# uart.net
KiCad netlist of a schematic drawn in Altium Designer
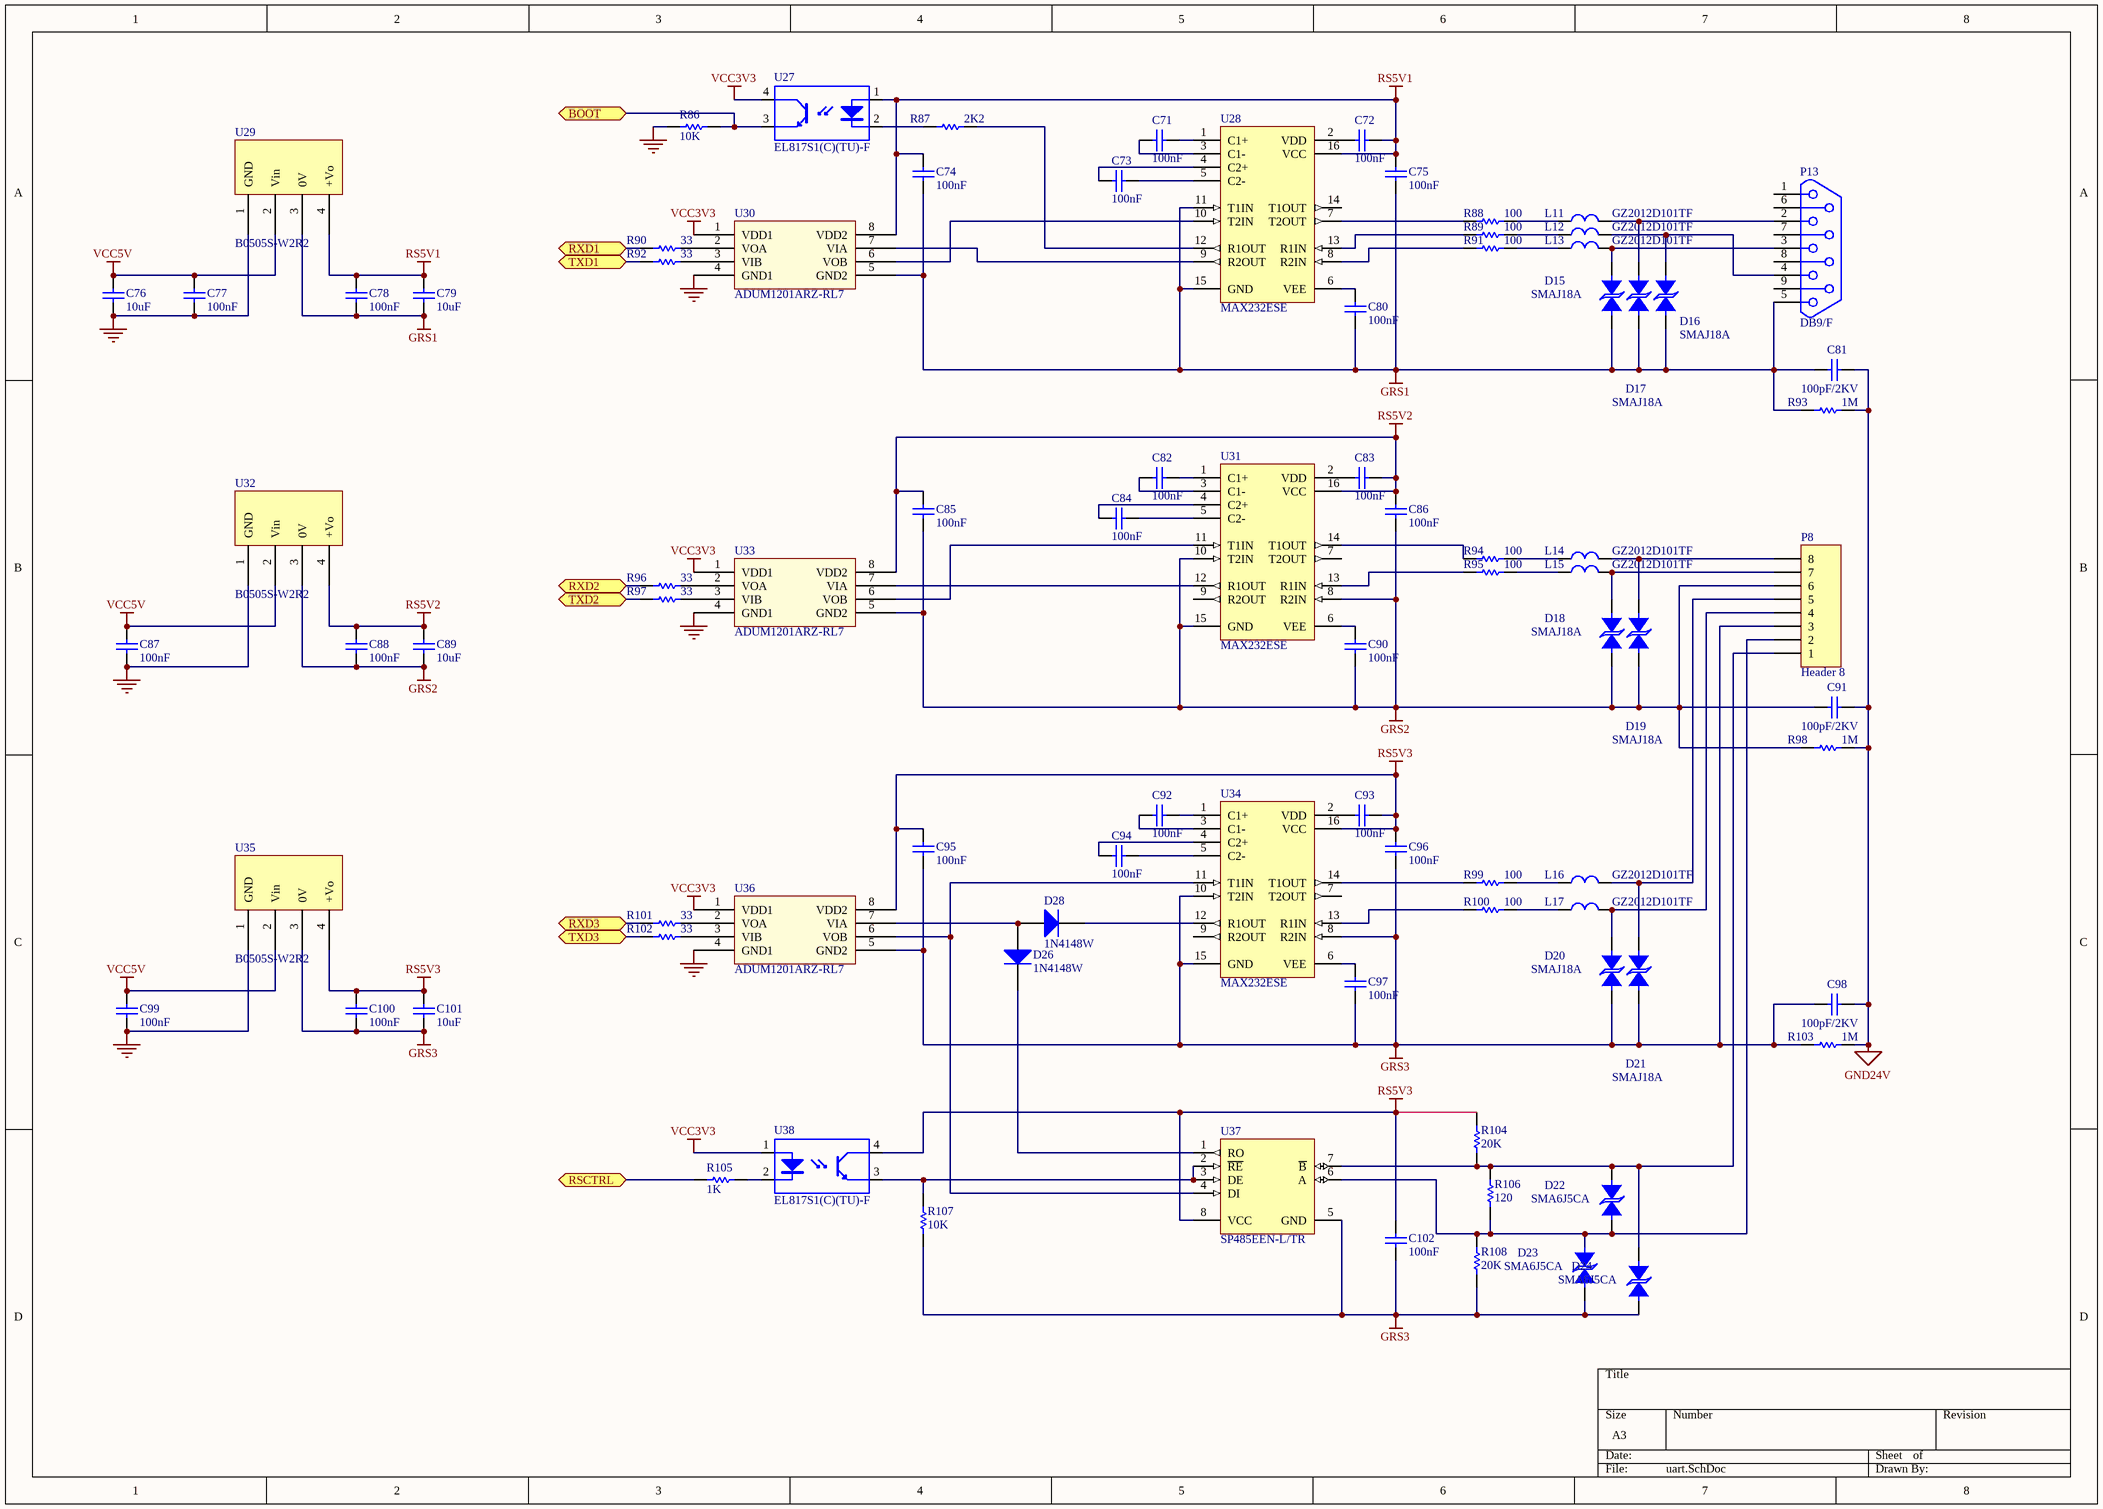
[diagram p0: uart.SchDoc]

(export (version "E")
  (design (tool "Eeschema 10.0.6"))
  (components
    (comp (ref "C71")
      (value "100nF")
      (footprint "0805_C")
      (description "贴片电容")
      (libsource (lib "Miscellaneous Devices LC") (part "0805 100nF(104) 10% 50V"))
    )
    (comp (ref "C72")
      (value "100nF")
      (footprint "0805_C")
      (description "贴片电容")
      (libsource (lib "Miscellaneous Devices LC") (part "0805 100nF(104) 10% 50V"))
    )
    (comp (ref "C73")
      (value "100nF")
      (footprint "0805_C")
      (description "贴片电容")
      (libsource (lib "Miscellaneous Devices LC") (part "0805 100nF(104) 10% 50V"))
    )
    (comp (ref "C74")
      (value "100nF")
      (footprint "0805_C")
      (description "贴片电容")
      (libsource (lib "Miscellaneous Devices LC") (part "0805 100nF(104) 10% 50V"))
    )
    (comp (ref "C75")
      (value "100nF")
      (footprint "0805_C")
      (description "贴片电容")
      (libsource (lib "Miscellaneous Devices LC") (part "0805 100nF(104) 10% 50V"))
    )
    (comp (ref "C76")
      (value "10uF")
      (footprint "0805_C")
      (description "贴片电容")
      (libsource (lib "Miscellaneous Devices LC") (part "0805 10uF (106) 10% 25V"))
    )
    (comp (ref "C77")
      (value "100nF")
      (footprint "0805_C")
      (description "贴片电容")
      (libsource (lib "Miscellaneous Devices LC") (part "0805 100nF(104) 10% 50V"))
    )
    (comp (ref "C78")
      (value "100nF")
      (footprint "0805_C")
      (description "贴片电容")
      (libsource (lib "Miscellaneous Devices LC") (part "0805 100nF(104) 10% 50V"))
    )
    (comp (ref "C79")
      (value "10uF")
      (footprint "0805_C")
      (description "贴片电容")
      (libsource (lib "Miscellaneous Devices LC") (part "0805 10uF (106) 10% 25V"))
    )
    (comp (ref "C80")
      (value "100nF")
      (footprint "0805_C")
      (description "贴片电容")
      (libsource (lib "Miscellaneous Devices LC") (part "0805 100nF(104) 10% 50V"))
    )
    (comp (ref "C81")
      (value "100pF/2KV")
      (footprint "1206_C")
      (description "Capacitor")
      (fields (field (name "PUBLISHER") "Altium Limited"))
      (libsource (lib "Miscellaneous Devices") (part "Cap"))
    )
    (comp (ref "C82")
      (value "100nF")
      (footprint "0805_C")
      (description "贴片电容")
      (libsource (lib "Miscellaneous Devices LC") (part "0805 100nF(104) 10% 50V"))
    )
    (comp (ref "C83")
      (value "100nF")
      (footprint "0805_C")
      (description "贴片电容")
      (libsource (lib "Miscellaneous Devices LC") (part "0805 100nF(104) 10% 50V"))
    )
    (comp (ref "C84")
      (value "100nF")
      (footprint "0805_C")
      (description "贴片电容")
      (libsource (lib "Miscellaneous Devices LC") (part "0805 100nF(104) 10% 50V"))
    )
    (comp (ref "C85")
      (value "100nF")
      (footprint "0805_C")
      (description "贴片电容")
      (libsource (lib "Miscellaneous Devices LC") (part "0805 100nF(104) 10% 50V"))
    )
    (comp (ref "C86")
      (value "100nF")
      (footprint "0805_C")
      (description "贴片电容")
      (libsource (lib "Miscellaneous Devices LC") (part "0805 100nF(104) 10% 50V"))
    )
    (comp (ref "C87")
      (value "100nF")
      (footprint "0805_C")
      (description "贴片电容")
      (libsource (lib "Miscellaneous Devices LC") (part "0805 100nF(104) 10% 50V"))
    )
    (comp (ref "C88")
      (value "100nF")
      (footprint "0805_C")
      (description "贴片电容")
      (libsource (lib "Miscellaneous Devices LC") (part "0805 100nF(104) 10% 50V"))
    )
    (comp (ref "C89")
      (value "10uF")
      (footprint "0805_C")
      (description "贴片电容")
      (libsource (lib "Miscellaneous Devices LC") (part "0805 10uF (106) 10% 25V"))
    )
    (comp (ref "C90")
      (value "100nF")
      (footprint "0805_C")
      (description "贴片电容")
      (libsource (lib "Miscellaneous Devices LC") (part "0805 100nF(104) 10% 50V"))
    )
    (comp (ref "C91")
      (value "100pF/2KV")
      (footprint "1206_C")
      (description "Capacitor")
      (fields (field (name "PUBLISHER") "Altium Limited"))
      (libsource (lib "Miscellaneous Devices") (part "Cap"))
    )
    (comp (ref "C92")
      (value "100nF")
      (footprint "0805_C")
      (description "贴片电容")
      (libsource (lib "Miscellaneous Devices LC") (part "0805 100nF(104) 10% 50V"))
    )
    (comp (ref "C93")
      (value "100nF")
      (footprint "0805_C")
      (description "贴片电容")
      (libsource (lib "Miscellaneous Devices LC") (part "0805 100nF(104) 10% 50V"))
    )
    (comp (ref "C94")
      (value "100nF")
      (footprint "0805_C")
      (description "贴片电容")
      (libsource (lib "Miscellaneous Devices LC") (part "0805 100nF(104) 10% 50V"))
    )
    (comp (ref "C95")
      (value "100nF")
      (footprint "0805_C")
      (description "贴片电容")
      (libsource (lib "Miscellaneous Devices LC") (part "0805 100nF(104) 10% 50V"))
    )
    (comp (ref "C96")
      (value "100nF")
      (footprint "0805_C")
      (description "贴片电容")
      (libsource (lib "Miscellaneous Devices LC") (part "0805 100nF(104) 10% 50V"))
    )
    (comp (ref "C97")
      (value "100nF")
      (footprint "0805_C")
      (description "贴片电容")
      (libsource (lib "Miscellaneous Devices LC") (part "0805 100nF(104) 10% 50V"))
    )
    (comp (ref "C98")
      (value "100pF/2KV")
      (footprint "1206_C")
      (description "Capacitor")
      (fields (field (name "PUBLISHER") "Altium Limited"))
      (libsource (lib "Miscellaneous Devices") (part "Cap"))
    )
    (comp (ref "C99")
      (value "100nF")
      (footprint "0805_C")
      (description "贴片电容")
      (libsource (lib "Miscellaneous Devices LC") (part "0805 100nF(104) 10% 50V"))
    )
    (comp (ref "C100")
      (value "100nF")
      (footprint "0805_C")
      (description "贴片电容")
      (libsource (lib "Miscellaneous Devices LC") (part "0805 100nF(104) 10% 50V"))
    )
    (comp (ref "C101")
      (value "10uF")
      (footprint "0805_C")
      (description "贴片电容")
      (libsource (lib "Miscellaneous Devices LC") (part "0805 10uF (106) 10% 25V"))
    )
    (comp (ref "C102")
      (value "100nF")
      (footprint "0805_C")
      (description "贴片电容")
      (libsource (lib "Miscellaneous Devices LC") (part "0805 100nF(104) 10% 50V"))
    )
    (comp (ref "D15")
      (value "SMAJ18A")
      (footprint "SMA")
      (description "1V5KE6V8CA")
      (libsource (lib "Schlib1") (part "Bidirectional DIODE TVS"))
    )
    (comp (ref "D16")
      (value "SMAJ18A")
      (footprint "SMA")
      (description "1V5KE6V8CA")
      (libsource (lib "Schlib1") (part "Bidirectional DIODE TVS"))
    )
    (comp (ref "D17")
      (value "SMAJ18A")
      (footprint "SMA")
      (description "1V5KE6V8CA")
      (libsource (lib "Schlib1") (part "Bidirectional DIODE TVS"))
    )
    (comp (ref "D18")
      (value "SMAJ18A")
      (footprint "SMA")
      (description "1V5KE6V8CA")
      (libsource (lib "Schlib1") (part "Bidirectional DIODE TVS"))
    )
    (comp (ref "D19")
      (value "SMAJ18A")
      (footprint "SMA")
      (description "1V5KE6V8CA")
      (libsource (lib "Schlib1") (part "Bidirectional DIODE TVS"))
    )
    (comp (ref "D20")
      (value "SMAJ18A")
      (footprint "SMA")
      (description "1V5KE6V8CA")
      (libsource (lib "Schlib1") (part "Bidirectional DIODE TVS"))
    )
    (comp (ref "D21")
      (value "SMAJ18A")
      (footprint "SMA")
      (description "1V5KE6V8CA")
      (libsource (lib "Schlib1") (part "Bidirectional DIODE TVS"))
    )
    (comp (ref "D22")
      (value "SMA6J5CA")
      (footprint "SMA")
      (description "1V5KE6V8CA")
      (libsource (lib "Schlib1") (part "Bidirectional DIODE TVS"))
    )
    (comp (ref "D23")
      (value "SMA6J5CA")
      (footprint "SMA")
      (description "1V5KE6V8CA")
      (libsource (lib "Schlib1") (part "Bidirectional DIODE TVS"))
    )
    (comp (ref "D24")
      (value "SMA6J5CA")
      (footprint "SMA")
      (description "1V5KE6V8CA")
      (libsource (lib "Schlib1") (part "Bidirectional DIODE TVS"))
    )
    (comp (ref "D26")
      (value "1N4148W")
      (footprint "SOD-123")
      (description "Default Diode")
      (fields (field (name "PUBLISHER") "Altium Limited"))
      (libsource (lib "Miscellaneous Devices") (part "Diode"))
    )
    (comp (ref "D28")
      (value "1N4148W")
      (footprint "SOD-123")
      (description "Default Diode")
      (fields (field (name "PUBLISHER") "Altium Limited"))
      (libsource (lib "Miscellaneous Devices") (part "Diode"))
    )
    (comp (ref "L11") (value "GZ2012D101TF") (footprint "0805_L") (libsource (lib "Devices") (part "L1")))
    (comp (ref "L12") (value "GZ2012D101TF") (footprint "0805_L") (libsource (lib "Devices") (part "L1")))
    (comp (ref "L13") (value "GZ2012D101TF") (footprint "0805_L") (libsource (lib "Devices") (part "L1")))
    (comp (ref "L14") (value "GZ2012D101TF") (footprint "0805_L") (libsource (lib "Devices") (part "L1")))
    (comp (ref "L15") (value "GZ2012D101TF") (footprint "0805_L") (libsource (lib "Devices") (part "L1")))
    (comp (ref "L16") (value "GZ2012D101TF") (footprint "0805_L") (libsource (lib "Devices") (part "L1")))
    (comp (ref "L17") (value "GZ2012D101TF") (footprint "0805_L") (libsource (lib "Devices") (part "L1")))
    (comp (ref "P8")
      (value "Header 8")
      (footprint "MC1.5/8-ST-3.81")
      (description "Header, 8-Pin")
      (fields (field (name "PUBLISHER") "Altium Limited"))
      (libsource (lib "Miscellaneous Connectors") (part "Header 8"))
    )
    (comp (ref "P13") (value "DB9/F") (footprint "DB9P/F") (libsource (lib "Devices") (part "DB9")))
    (comp (ref "R86")
      (value "10K")
      (footprint "0805_R")
      (description "Resistor")
      (fields (field (name "PUBLISHER") "Altium Limited"))
      (libsource (lib "Miscellaneous Devices") (part "Res1"))
    )
    (comp (ref "R87")
      (value "2K2")
      (footprint "0805_R")
      (description "Resistor")
      (fields (field (name "PUBLISHER") "Altium Limited"))
      (libsource (lib "Miscellaneous Devices") (part "Res1"))
    )
    (comp (ref "R88")
      (value "100")
      (footprint "0805_R")
      (description "Resistor")
      (fields (field (name "PUBLISHER") "Altium Limited"))
      (libsource (lib "Miscellaneous Devices") (part "Res1"))
    )
    (comp (ref "R89")
      (value "100")
      (footprint "0805_R")
      (description "Resistor")
      (fields (field (name "PUBLISHER") "Altium Limited"))
      (libsource (lib "Miscellaneous Devices") (part "Res1"))
    )
    (comp (ref "R90")
      (value "33")
      (footprint "0805_R")
      (description "Resistor")
      (fields (field (name "PUBLISHER") "Altium Limited"))
      (libsource (lib "Miscellaneous Devices") (part "Res1"))
    )
    (comp (ref "R91")
      (value "100")
      (footprint "0805_R")
      (description "Resistor")
      (fields (field (name "PUBLISHER") "Altium Limited"))
      (libsource (lib "Miscellaneous Devices") (part "Res1"))
    )
    (comp (ref "R92")
      (value "33")
      (footprint "0805_R")
      (description "Resistor")
      (fields (field (name "PUBLISHER") "Altium Limited"))
      (libsource (lib "Miscellaneous Devices") (part "Res1"))
    )
    (comp (ref "R93")
      (value "1M")
      (footprint "1206_R")
      (description "Resistor")
      (fields (field (name "PUBLISHER") "Altium Limited"))
      (libsource (lib "Miscellaneous Devices") (part "Res1"))
    )
    (comp (ref "R94")
      (value "100")
      (footprint "0805_R")
      (description "Resistor")
      (fields (field (name "PUBLISHER") "Altium Limited"))
      (libsource (lib "Miscellaneous Devices") (part "Res1"))
    )
    (comp (ref "R95")
      (value "100")
      (footprint "0805_R")
      (description "Resistor")
      (fields (field (name "PUBLISHER") "Altium Limited"))
      (libsource (lib "Miscellaneous Devices") (part "Res1"))
    )
    (comp (ref "R96")
      (value "33")
      (footprint "0805_R")
      (description "Resistor")
      (fields (field (name "PUBLISHER") "Altium Limited"))
      (libsource (lib "Miscellaneous Devices") (part "Res1"))
    )
    (comp (ref "R97")
      (value "33")
      (footprint "0805_R")
      (description "Resistor")
      (fields (field (name "PUBLISHER") "Altium Limited"))
      (libsource (lib "Miscellaneous Devices") (part "Res1"))
    )
    (comp (ref "R98")
      (value "1M")
      (footprint "1206_R")
      (description "Resistor")
      (fields (field (name "PUBLISHER") "Altium Limited"))
      (libsource (lib "Miscellaneous Devices") (part "Res1"))
    )
    (comp (ref "R99")
      (value "100")
      (footprint "0805_R")
      (description "Resistor")
      (fields (field (name "PUBLISHER") "Altium Limited"))
      (libsource (lib "Miscellaneous Devices") (part "Res1"))
    )
    (comp (ref "R100")
      (value "100")
      (footprint "0805_R")
      (description "Resistor")
      (fields (field (name "PUBLISHER") "Altium Limited"))
      (libsource (lib "Miscellaneous Devices") (part "Res1"))
    )
    (comp (ref "R101")
      (value "33")
      (footprint "0805_R")
      (description "Resistor")
      (fields (field (name "PUBLISHER") "Altium Limited"))
      (libsource (lib "Miscellaneous Devices") (part "Res1"))
    )
    (comp (ref "R102")
      (value "33")
      (footprint "0805_R")
      (description "Resistor")
      (fields (field (name "PUBLISHER") "Altium Limited"))
      (libsource (lib "Miscellaneous Devices") (part "Res1"))
    )
    (comp (ref "R103")
      (value "1M")
      (footprint "1206_R")
      (description "Resistor")
      (fields (field (name "PUBLISHER") "Altium Limited"))
      (libsource (lib "Miscellaneous Devices") (part "Res1"))
    )
    (comp (ref "R104")
      (value "20K")
      (footprint "0805_R")
      (description "Resistor")
      (fields (field (name "PUBLISHER") "Altium Limited"))
      (libsource (lib "Miscellaneous Devices") (part "Res1"))
    )
    (comp (ref "R105")
      (value "1K")
      (footprint "0805_R")
      (description "Resistor")
      (fields (field (name "PUBLISHER") "Altium Limited"))
      (libsource (lib "Miscellaneous Devices") (part "Res1"))
    )
    (comp (ref "R106")
      (value "120")
      (footprint "0805_R")
      (description "Resistor")
      (fields (field (name "PUBLISHER") "Altium Limited"))
      (libsource (lib "Miscellaneous Devices") (part "Res1"))
    )
    (comp (ref "R107")
      (value "10K")
      (footprint "0805_R")
      (description "Resistor")
      (fields (field (name "PUBLISHER") "Altium Limited"))
      (libsource (lib "Miscellaneous Devices") (part "Res1"))
    )
    (comp (ref "R108")
      (value "20K")
      (footprint "0805_R")
      (description "Resistor")
      (fields (field (name "PUBLISHER") "Altium Limited"))
      (libsource (lib "Miscellaneous Devices") (part "Res1"))
    )
    (comp (ref "U27")
      (value "EL817S1(C)(TU)-F")
      (footprint "LC-SMD-4")
      (libsource (lib "") (part "TLP521_1"))
    )
    (comp (ref "U28")
      (value "MAX232ESE")
      (footprint "SOIC-16_150mil")
      (description "RS232")
      (libsource (lib "Miscellaneous Devices LC") (part "MAX232ESE_[C26860]"))
    )
    (comp (ref "U29")
      (value "B0505S-W2R2")
      (footprint "MORNSUN-BM")
      (description "MORNSUN Fixed input,Isolated,Unregulated Series DC/DC")
      (libsource (lib "稳压器件") (part "MORNSUN-BM"))
    )
    (comp (ref "U30")
      (value "ADUM1201ARZ-RL7")
      (footprint "SOIC-8_150mil")
      (description "隔离器")
      (libsource (lib "IC") (part "ADUM1201ARZ-RL7_[C9669]"))
    )
    (comp (ref "U31")
      (value "MAX232ESE")
      (footprint "SOIC-16_150mil")
      (description "RS232")
      (libsource (lib "Miscellaneous Devices LC") (part "MAX232ESE_[C26860]"))
    )
    (comp (ref "U32")
      (value "B0505S-W2R2")
      (footprint "MORNSUN-BM")
      (description "MORNSUN Fixed input,Isolated,Unregulated Series DC/DC")
      (libsource (lib "稳压器件") (part "MORNSUN-BM"))
    )
    (comp (ref "U33")
      (value "ADUM1201ARZ-RL7")
      (footprint "SOIC-8_150mil")
      (description "隔离器")
      (libsource (lib "IC") (part "ADUM1201ARZ-RL7_[C9669]"))
    )
    (comp (ref "U34")
      (value "MAX232ESE")
      (footprint "SOIC-16_150mil")
      (description "RS232")
      (libsource (lib "Miscellaneous Devices LC") (part "MAX232ESE_[C26860]"))
    )
    (comp (ref "U35")
      (value "B0505S-W2R2")
      (footprint "MORNSUN-BM")
      (description "MORNSUN Fixed input,Isolated,Unregulated Series DC/DC")
      (libsource (lib "稳压器件") (part "MORNSUN-BM"))
    )
    (comp (ref "U36")
      (value "ADUM1201ARZ-RL7")
      (footprint "SOIC-8_150mil")
      (description "隔离器")
      (libsource (lib "IC") (part "ADUM1201ARZ-RL7_[C9669]"))
    )
    (comp (ref "U37")
      (value "SP485EEN-L/TR")
      (footprint "SOIC-8_150mil")
      (description "RS-485/RS-422")
      (libsource (lib "Miscellaneous Devices LC") (part "SP485EEN-L/TR_[C6855]"))
    )
    (comp (ref "U38")
      (value "EL817S1(C)(TU)-F")
      (footprint "LC-SMD-4")
      (libsource (lib "IC") (part "TLP521"))
    )
  )
  (nets
    (net (code "1") (name "/BOOT") (class "Default")
      (node (ref "R86") (pin "2") (pinfunction "2_2") (pintype "passive"))
      (node (ref "U27") (pin "3") (pinfunction "E_3") (pintype "passive"))
    )
    (net (code "2") (name "/RSCTRL") (class "Default")
      (node (ref "R105") (pin "1") (pinfunction "1_1") (pintype "passive"))
    )
    (net (code "3") (name "/RXD1") (class "Default")
      (node (ref "R90") (pin "1") (pinfunction "1_1") (pintype "passive"))
    )
    (net (code "4") (name "/RXD2") (class "Default")
      (node (ref "R96") (pin "1") (pinfunction "1_1") (pintype "passive"))
    )
    (net (code "5") (name "/RXD3") (class "Default")
      (node (ref "R101") (pin "1") (pinfunction "1_1") (pintype "passive"))
    )
    (net (code "6") (name "/TXD1") (class "Default")
      (node (ref "R92") (pin "2") (pinfunction "2_2") (pintype "passive"))
    )
    (net (code "7") (name "/TXD2") (class "Default")
      (node (ref "R97") (pin "2") (pinfunction "2_2") (pintype "passive"))
    )
    (net (code "8") (name "/TXD3") (class "Default")
      (node (ref "R102") (pin "2") (pinfunction "2_2") (pintype "passive"))
    )
    (net (code "9") (name "GND") (class "Default")
      (node (ref "C76") (pin "1") (pinfunction "1_1") (pintype "passive"))
      (node (ref "C77") (pin "2") (pinfunction "2_2") (pintype "passive"))
      (node (ref "C87") (pin "2") (pinfunction "2_2") (pintype "passive"))
      (node (ref "C99") (pin "2") (pinfunction "2_2") (pintype "passive"))
      (node (ref "R86") (pin "1") (pinfunction "1_1") (pintype "passive"))
      (node (ref "U29") (pin "1") (pinfunction "GND_1") (pintype "passive"))
      (node (ref "U30") (pin "4") (pinfunction "GND1_4") (pintype "passive"))
      (node (ref "U32") (pin "1") (pinfunction "GND_1") (pintype "passive"))
      (node (ref "U33") (pin "4") (pinfunction "GND1_4") (pintype "passive"))
      (node (ref "U35") (pin "1") (pinfunction "GND_1") (pintype "passive"))
      (node (ref "U36") (pin "4") (pinfunction "GND1_4") (pintype "passive"))
    )
    (net (code "10") (name "GND24V") (class "Default")
      (node (ref "C81") (pin "2") (pinfunction "2_2") (pintype "passive"))
      (node (ref "C91") (pin "2") (pinfunction "2_2") (pintype "passive"))
      (node (ref "C98") (pin "2") (pinfunction "2_2") (pintype "passive"))
      (node (ref "R103") (pin "2") (pinfunction "2_2") (pintype "passive"))
      (node (ref "R93") (pin "2") (pinfunction "2_2") (pintype "passive"))
      (node (ref "R98") (pin "2") (pinfunction "2_2") (pintype "passive"))
    )
    (net (code "11") (name "GRS1") (class "Default")
      (node (ref "C74") (pin "2") (pinfunction "2_2") (pintype "passive"))
      (node (ref "C75") (pin "2") (pinfunction "2_2") (pintype "passive"))
      (node (ref "C78") (pin "2") (pinfunction "2_2") (pintype "passive"))
      (node (ref "C79") (pin "1") (pinfunction "1_1") (pintype "passive"))
      (node (ref "C80") (pin "1") (pinfunction "1_1") (pintype "passive"))
      (node (ref "C81") (pin "1") (pinfunction "1_1") (pintype "passive"))
      (node (ref "D15") (pin "1") (pinfunction "ANODE_1") (pintype "passive"))
      (node (ref "D16") (pin "1") (pinfunction "ANODE_1") (pintype "passive"))
      (node (ref "D17") (pin "1") (pinfunction "ANODE_1") (pintype "passive"))
      (node (ref "P13") (pin "5") (pinfunction "5_5") (pintype "passive"))
      (node (ref "R93") (pin "1") (pinfunction "1_1") (pintype "passive"))
      (node (ref "U28") (pin "11") (pinfunction "T1IN_11") (pintype "input"))
      (node (ref "U28") (pin "15") (pinfunction "GND_15") (pintype "power_in"))
      (node (ref "U29") (pin "3") (pinfunction "0V_3") (pintype "passive"))
      (node (ref "U30") (pin "5") (pinfunction "GND2_5") (pintype "passive"))
    )
    (net (code "12") (name "GRS2") (class "Default")
      (node (ref "C85") (pin "2") (pinfunction "2_2") (pintype "passive"))
      (node (ref "C86") (pin "2") (pinfunction "2_2") (pintype "passive"))
      (node (ref "C88") (pin "2") (pinfunction "2_2") (pintype "passive"))
      (node (ref "C89") (pin "1") (pinfunction "1_1") (pintype "passive"))
      (node (ref "C90") (pin "1") (pinfunction "1_1") (pintype "passive"))
      (node (ref "C91") (pin "1") (pinfunction "1_1") (pintype "passive"))
      (node (ref "D18") (pin "1") (pinfunction "ANODE_1") (pintype "passive"))
      (node (ref "D19") (pin "1") (pinfunction "ANODE_1") (pintype "passive"))
      (node (ref "P8") (pin "6") (pinfunction "6_6") (pintype "passive"))
      (node (ref "R98") (pin "1") (pinfunction "1_1") (pintype "passive"))
      (node (ref "U31") (pin "10") (pinfunction "T2IN_10") (pintype "input"))
      (node (ref "U31") (pin "15") (pinfunction "GND_15") (pintype "power_in"))
      (node (ref "U31") (pin "8") (pinfunction "R2IN_8") (pintype "input"))
      (node (ref "U32") (pin "3") (pinfunction "0V_3") (pintype "passive"))
      (node (ref "U33") (pin "5") (pinfunction "GND2_5") (pintype "passive"))
    )
    (net (code "13") (name "GRS3") (class "Default")
      (node (ref "C100") (pin "2") (pinfunction "2_2") (pintype "passive"))
      (node (ref "C101") (pin "1") (pinfunction "1_1") (pintype "passive"))
      (node (ref "C102") (pin "1") (pinfunction "1_1") (pintype "passive"))
      (node (ref "C95") (pin "2") (pinfunction "2_2") (pintype "passive"))
      (node (ref "C96") (pin "2") (pinfunction "2_2") (pintype "passive"))
      (node (ref "C97") (pin "1") (pinfunction "1_1") (pintype "passive"))
      (node (ref "C98") (pin "1") (pinfunction "1_1") (pintype "passive"))
      (node (ref "D20") (pin "1") (pinfunction "ANODE_1") (pintype "passive"))
      (node (ref "D21") (pin "1") (pinfunction "ANODE_1") (pintype "passive"))
      (node (ref "D23") (pin "1") (pinfunction "ANODE_1") (pintype "passive"))
      (node (ref "D24") (pin "1") (pinfunction "ANODE_1") (pintype "passive"))
      (node (ref "P8") (pin "3") (pinfunction "3_3") (pintype "passive"))
      (node (ref "R103") (pin "1") (pinfunction "1_1") (pintype "passive"))
      (node (ref "R107") (pin "2") (pinfunction "2_2") (pintype "passive"))
      (node (ref "R108") (pin "2") (pinfunction "2_2") (pintype "passive"))
      (node (ref "U34") (pin "10") (pinfunction "T2IN_10") (pintype "input"))
      (node (ref "U34") (pin "15") (pinfunction "GND_15") (pintype "power_in"))
      (node (ref "U34") (pin "8") (pinfunction "R2IN_8") (pintype "input"))
      (node (ref "U35") (pin "3") (pinfunction "0V_3") (pintype "passive"))
      (node (ref "U36") (pin "5") (pinfunction "GND2_5") (pintype "passive"))
      (node (ref "U37") (pin "5") (pinfunction "GND_5") (pintype "power_in"))
    )
    (net (code "14") (name "Net-(D15-CATHODE)") (class "Default")
      (node (ref "D15") (pin "2") (pinfunction "CATHODE_2") (pintype "passive"))
      (node (ref "L13") (pin "2") (pinfunction "2_2") (pintype "passive"))
      (node (ref "P13") (pin "3") (pinfunction "3_3") (pintype "passive"))
    )
    (net (code "15") (name "Net-(D16-CATHODE)") (class "Default")
      (node (ref "D16") (pin "2") (pinfunction "CATHODE_2") (pintype "passive"))
      (node (ref "L12") (pin "2") (pinfunction "2_2") (pintype "passive"))
      (node (ref "P13") (pin "4") (pinfunction "4_4") (pintype "passive"))
    )
    (net (code "16") (name "Net-(D17-CATHODE)") (class "Default")
      (node (ref "D17") (pin "2") (pinfunction "CATHODE_2") (pintype "passive"))
      (node (ref "L11") (pin "2") (pinfunction "2_2") (pintype "passive"))
      (node (ref "P13") (pin "2") (pinfunction "2_2") (pintype "passive"))
    )
    (net (code "17") (name "Net-(D18-CATHODE)") (class "Default")
      (node (ref "D18") (pin "2") (pinfunction "CATHODE_2") (pintype "passive"))
      (node (ref "L15") (pin "2") (pinfunction "2_2") (pintype "passive"))
      (node (ref "P8") (pin "7") (pinfunction "7_7") (pintype "passive"))
    )
    (net (code "18") (name "Net-(D19-CATHODE)") (class "Default")
      (node (ref "D19") (pin "2") (pinfunction "CATHODE_2") (pintype "passive"))
      (node (ref "L14") (pin "2") (pinfunction "2_2") (pintype "passive"))
      (node (ref "P8") (pin "8") (pinfunction "8_8") (pintype "passive"))
    )
    (net (code "19") (name "Net-(D20-CATHODE)") (class "Default")
      (node (ref "D20") (pin "2") (pinfunction "CATHODE_2") (pintype "passive"))
      (node (ref "L17") (pin "2") (pinfunction "2_2") (pintype "passive"))
      (node (ref "P8") (pin "4") (pinfunction "4_4") (pintype "passive"))
    )
    (net (code "20") (name "Net-(D21-CATHODE)") (class "Default")
      (node (ref "D21") (pin "2") (pinfunction "CATHODE_2") (pintype "passive"))
      (node (ref "L16") (pin "2") (pinfunction "2_2") (pintype "passive"))
      (node (ref "P8") (pin "5") (pinfunction "5_5") (pintype "passive"))
    )
    (net (code "21") (name "Net-(D22-ANODE)") (class "Default")
      (node (ref "D22") (pin "1") (pinfunction "ANODE_1") (pintype "passive"))
      (node (ref "D23") (pin "2") (pinfunction "CATHODE_2") (pintype "passive"))
      (node (ref "P8") (pin "2") (pinfunction "2_2") (pintype "passive"))
      (node (ref "R106") (pin "2") (pinfunction "2_2") (pintype "passive"))
      (node (ref "R108") (pin "1") (pinfunction "1_1") (pintype "passive"))
      (node (ref "U37") (pin "6") (pinfunction "A_6") (pintype "bidirectional"))
    )
    (net (code "22") (name "Net-(D22-CATHODE)") (class "Default")
      (node (ref "D22") (pin "2") (pinfunction "CATHODE_2") (pintype "passive"))
      (node (ref "D24") (pin "2") (pinfunction "CATHODE_2") (pintype "passive"))
      (node (ref "P8") (pin "1") (pinfunction "1_1") (pintype "passive"))
      (node (ref "R104") (pin "2") (pinfunction "2_2") (pintype "passive"))
      (node (ref "R106") (pin "1") (pinfunction "1_1") (pintype "passive"))
      (node (ref "U37") (pin "7") (pinfunction "~{B}_7") (pintype "bidirectional"))
    )
    (net (code "23") (name "Net-(D26-A)") (class "Default")
      (node (ref "D26") (pin "1") (pinfunction "A_1") (pintype "passive"))
      (node (ref "D28") (pin "1") (pinfunction "A_1") (pintype "passive"))
      (node (ref "U36") (pin "7") (pinfunction "VIA_7") (pintype "passive"))
    )
    (net (code "24") (name "Net-(D26-K)") (class "Default")
      (node (ref "D26") (pin "2") (pinfunction "K_2") (pintype "passive"))
      (node (ref "U37") (pin "1") (pinfunction "RO_1") (pintype "output"))
    )
    (net (code "25") (name "Net-(D28-K)") (class "Default")
      (node (ref "D28") (pin "2") (pinfunction "K_2") (pintype "passive"))
      (node (ref "U34") (pin "12") (pinfunction "R1OUT_12") (pintype "output"))
    )
    (net (code "26") (name "Net-(L11-Pad1)") (class "Default")
      (node (ref "L11") (pin "1") (pinfunction "1_1") (pintype "passive"))
      (node (ref "R88") (pin "1") (pinfunction "1_1") (pintype "passive"))
    )
    (net (code "27") (name "Net-(L12-Pad1)") (class "Default")
      (node (ref "L12") (pin "1") (pinfunction "1_1") (pintype "passive"))
      (node (ref "R89") (pin "1") (pinfunction "1_1") (pintype "passive"))
    )
    (net (code "28") (name "Net-(L13-Pad1)") (class "Default")
      (node (ref "L13") (pin "1") (pinfunction "1_1") (pintype "passive"))
      (node (ref "R91") (pin "1") (pinfunction "1_1") (pintype "passive"))
    )
    (net (code "29") (name "Net-(L14-Pad1)") (class "Default")
      (node (ref "L14") (pin "1") (pinfunction "1_1") (pintype "passive"))
      (node (ref "R94") (pin "1") (pinfunction "1_1") (pintype "passive"))
    )
    (net (code "30") (name "Net-(L15-Pad1)") (class "Default")
      (node (ref "L15") (pin "1") (pinfunction "1_1") (pintype "passive"))
      (node (ref "R95") (pin "1") (pinfunction "1_1") (pintype "passive"))
    )
    (net (code "31") (name "Net-(L16-Pad1)") (class "Default")
      (node (ref "L16") (pin "1") (pinfunction "1_1") (pintype "passive"))
      (node (ref "R99") (pin "1") (pinfunction "1_1") (pintype "passive"))
    )
    (net (code "32") (name "Net-(L17-Pad1)") (class "Default")
      (node (ref "L17") (pin "1") (pinfunction "1_1") (pintype "passive"))
      (node (ref "R100") (pin "1") (pinfunction "1_1") (pintype "passive"))
    )
    (net (code "33") (name "Net-(U27-K)") (class "Default")
      (node (ref "R87") (pin "1") (pinfunction "1_1") (pintype "passive"))
      (node (ref "U27") (pin "2") (pinfunction "K_2") (pintype "passive"))
    )
    (net (code "34") (name "Net-(U28-C1+)") (class "Default")
      (node (ref "C71") (pin "1") (pinfunction "1_1") (pintype "passive"))
      (node (ref "U28") (pin "1") (pinfunction "C1+_1") (pintype "passive"))
    )
    (net (code "35") (name "Net-(U28-C1-)") (class "Default")
      (node (ref "C71") (pin "2") (pinfunction "2_2") (pintype "passive"))
      (node (ref "U28") (pin "3") (pinfunction "C1-_3") (pintype "passive"))
    )
    (net (code "36") (name "Net-(U28-C2+)") (class "Default")
      (node (ref "C73") (pin "2") (pinfunction "2_2") (pintype "passive"))
      (node (ref "U28") (pin "4") (pinfunction "C2+_4") (pintype "passive"))
    )
    (net (code "37") (name "Net-(U28-C2-)") (class "Default")
      (node (ref "C73") (pin "1") (pinfunction "1_1") (pintype "passive"))
      (node (ref "U28") (pin "5") (pinfunction "C2-_5") (pintype "passive"))
    )
    (net (code "38") (name "Net-(U28-R1IN)") (class "Default")
      (node (ref "R89") (pin "2") (pinfunction "2_2") (pintype "passive"))
      (node (ref "U28") (pin "13") (pinfunction "R1IN_13") (pintype "input"))
    )
    (net (code "39") (name "Net-(U28-R1OUT)") (class "Default")
      (node (ref "R87") (pin "2") (pinfunction "2_2") (pintype "passive"))
      (node (ref "U28") (pin "12") (pinfunction "R1OUT_12") (pintype "output"))
    )
    (net (code "40") (name "Net-(U28-R2IN)") (class "Default")
      (node (ref "R91") (pin "2") (pinfunction "2_2") (pintype "passive"))
      (node (ref "U28") (pin "8") (pinfunction "R2IN_8") (pintype "input"))
    )
    (net (code "41") (name "Net-(U28-R2OUT)") (class "Default")
      (node (ref "U28") (pin "9") (pinfunction "R2OUT_9") (pintype "output"))
      (node (ref "U30") (pin "7") (pinfunction "VIA_7") (pintype "passive"))
    )
    (net (code "42") (name "Net-(U28-T2IN)") (class "Default")
      (node (ref "U28") (pin "10") (pinfunction "T2IN_10") (pintype "input"))
      (node (ref "U30") (pin "6") (pinfunction "VOB_6") (pintype "passive"))
    )
    (net (code "43") (name "Net-(U28-T2OUT)") (class "Default")
      (node (ref "R88") (pin "2") (pinfunction "2_2") (pintype "passive"))
      (node (ref "U28") (pin "7") (pinfunction "T2OUT_7") (pintype "output"))
    )
    (net (code "44") (name "Net-(U28-VDD)") (class "Default")
      (node (ref "C72") (pin "2") (pinfunction "2_2") (pintype "passive"))
      (node (ref "U28") (pin "2") (pinfunction "VDD_2") (pintype "power_in"))
    )
    (net (code "45") (name "Net-(U28-VEE)") (class "Default")
      (node (ref "C80") (pin "2") (pinfunction "2_2") (pintype "passive"))
      (node (ref "U28") (pin "6") (pinfunction "VEE_6") (pintype "power_in"))
    )
    (net (code "46") (name "Net-(U30-VIB)") (class "Default")
      (node (ref "R92") (pin "1") (pinfunction "1_1") (pintype "passive"))
      (node (ref "U30") (pin "3") (pinfunction "VIB_3") (pintype "passive"))
    )
    (net (code "47") (name "Net-(U30-VOA)") (class "Default")
      (node (ref "R90") (pin "2") (pinfunction "2_2") (pintype "passive"))
      (node (ref "U30") (pin "2") (pinfunction "VOA_2") (pintype "passive"))
    )
    (net (code "48") (name "Net-(U31-C1+)") (class "Default")
      (node (ref "C82") (pin "1") (pinfunction "1_1") (pintype "passive"))
      (node (ref "U31") (pin "1") (pinfunction "C1+_1") (pintype "passive"))
    )
    (net (code "49") (name "Net-(U31-C1-)") (class "Default")
      (node (ref "C82") (pin "2") (pinfunction "2_2") (pintype "passive"))
      (node (ref "U31") (pin "3") (pinfunction "C1-_3") (pintype "passive"))
    )
    (net (code "50") (name "Net-(U31-C2+)") (class "Default")
      (node (ref "C84") (pin "2") (pinfunction "2_2") (pintype "passive"))
      (node (ref "U31") (pin "4") (pinfunction "C2+_4") (pintype "passive"))
    )
    (net (code "51") (name "Net-(U31-C2-)") (class "Default")
      (node (ref "C84") (pin "1") (pinfunction "1_1") (pintype "passive"))
      (node (ref "U31") (pin "5") (pinfunction "C2-_5") (pintype "passive"))
    )
    (net (code "52") (name "Net-(U31-R1IN)") (class "Default")
      (node (ref "R95") (pin "2") (pinfunction "2_2") (pintype "passive"))
      (node (ref "U31") (pin "13") (pinfunction "R1IN_13") (pintype "input"))
    )
    (net (code "53") (name "Net-(U31-R1OUT)") (class "Default")
      (node (ref "U31") (pin "12") (pinfunction "R1OUT_12") (pintype "output"))
      (node (ref "U33") (pin "7") (pinfunction "VIA_7") (pintype "passive"))
    )
    (net (code "54") (name "Net-(U31-T1IN)") (class "Default")
      (node (ref "U31") (pin "11") (pinfunction "T1IN_11") (pintype "input"))
      (node (ref "U33") (pin "6") (pinfunction "VOB_6") (pintype "passive"))
    )
    (net (code "55") (name "Net-(U31-T1OUT)") (class "Default")
      (node (ref "R94") (pin "2") (pinfunction "2_2") (pintype "passive"))
      (node (ref "U31") (pin "14") (pinfunction "T1OUT_14") (pintype "output"))
    )
    (net (code "56") (name "Net-(U31-VDD)") (class "Default")
      (node (ref "C83") (pin "2") (pinfunction "2_2") (pintype "passive"))
      (node (ref "U31") (pin "2") (pinfunction "VDD_2") (pintype "power_in"))
    )
    (net (code "57") (name "Net-(U31-VEE)") (class "Default")
      (node (ref "C90") (pin "2") (pinfunction "2_2") (pintype "passive"))
      (node (ref "U31") (pin "6") (pinfunction "VEE_6") (pintype "power_in"))
    )
    (net (code "58") (name "Net-(U33-VIB)") (class "Default")
      (node (ref "R97") (pin "1") (pinfunction "1_1") (pintype "passive"))
      (node (ref "U33") (pin "3") (pinfunction "VIB_3") (pintype "passive"))
    )
    (net (code "59") (name "Net-(U33-VOA)") (class "Default")
      (node (ref "R96") (pin "2") (pinfunction "2_2") (pintype "passive"))
      (node (ref "U33") (pin "2") (pinfunction "VOA_2") (pintype "passive"))
    )
    (net (code "60") (name "Net-(U34-C1+)") (class "Default")
      (node (ref "C92") (pin "1") (pinfunction "1_1") (pintype "passive"))
      (node (ref "U34") (pin "1") (pinfunction "C1+_1") (pintype "passive"))
    )
    (net (code "61") (name "Net-(U34-C1-)") (class "Default")
      (node (ref "C92") (pin "2") (pinfunction "2_2") (pintype "passive"))
      (node (ref "U34") (pin "3") (pinfunction "C1-_3") (pintype "passive"))
    )
    (net (code "62") (name "Net-(U34-C2+)") (class "Default")
      (node (ref "C94") (pin "2") (pinfunction "2_2") (pintype "passive"))
      (node (ref "U34") (pin "4") (pinfunction "C2+_4") (pintype "passive"))
    )
    (net (code "63") (name "Net-(U34-C2-)") (class "Default")
      (node (ref "C94") (pin "1") (pinfunction "1_1") (pintype "passive"))
      (node (ref "U34") (pin "5") (pinfunction "C2-_5") (pintype "passive"))
    )
    (net (code "64") (name "Net-(U34-R1IN)") (class "Default")
      (node (ref "R100") (pin "2") (pinfunction "2_2") (pintype "passive"))
      (node (ref "U34") (pin "13") (pinfunction "R1IN_13") (pintype "input"))
    )
    (net (code "65") (name "Net-(U34-T1IN)") (class "Default")
      (node (ref "U34") (pin "11") (pinfunction "T1IN_11") (pintype "input"))
      (node (ref "U36") (pin "6") (pinfunction "VOB_6") (pintype "passive"))
      (node (ref "U37") (pin "4") (pinfunction "DI_4") (pintype "input"))
    )
    (net (code "66") (name "Net-(U34-T1OUT)") (class "Default")
      (node (ref "R99") (pin "2") (pinfunction "2_2") (pintype "passive"))
      (node (ref "U34") (pin "14") (pinfunction "T1OUT_14") (pintype "output"))
    )
    (net (code "67") (name "Net-(U34-VDD)") (class "Default")
      (node (ref "C93") (pin "2") (pinfunction "2_2") (pintype "passive"))
      (node (ref "U34") (pin "2") (pinfunction "VDD_2") (pintype "power_in"))
    )
    (net (code "68") (name "Net-(U34-VEE)") (class "Default")
      (node (ref "C97") (pin "2") (pinfunction "2_2") (pintype "passive"))
      (node (ref "U34") (pin "6") (pinfunction "VEE_6") (pintype "power_in"))
    )
    (net (code "69") (name "Net-(U36-VIB)") (class "Default")
      (node (ref "R102") (pin "1") (pinfunction "1_1") (pintype "passive"))
      (node (ref "U36") (pin "3") (pinfunction "VIB_3") (pintype "passive"))
    )
    (net (code "70") (name "Net-(U36-VOA)") (class "Default")
      (node (ref "R101") (pin "2") (pinfunction "2_2") (pintype "passive"))
      (node (ref "U36") (pin "2") (pinfunction "VOA_2") (pintype "passive"))
    )
    (net (code "71") (name "Net-(U37-DE)") (class "Default")
      (node (ref "R107") (pin "1") (pinfunction "1_1") (pintype "passive"))
      (node (ref "U37") (pin "2") (pinfunction "~{RE}_2") (pintype "input"))
      (node (ref "U37") (pin "3") (pinfunction "DE_3") (pintype "input"))
      (node (ref "U38") (pin "3") (pinfunction "E_3") (pintype "passive"))
    )
    (net (code "72") (name "Net-(U38-K)") (class "Default")
      (node (ref "R105") (pin "2") (pinfunction "2_2") (pintype "passive"))
      (node (ref "U38") (pin "2") (pinfunction "K_2") (pintype "passive"))
    )
    (net (code "73") (name "RS5V1") (class "Default")
      (node (ref "C72") (pin "1") (pinfunction "1_1") (pintype "passive"))
      (node (ref "C74") (pin "1") (pinfunction "1_1") (pintype "passive"))
      (node (ref "C75") (pin "1") (pinfunction "1_1") (pintype "passive"))
      (node (ref "C78") (pin "1") (pinfunction "1_1") (pintype "passive"))
      (node (ref "C79") (pin "2") (pinfunction "2_2") (pintype "passive"))
      (node (ref "U27") (pin "1") (pinfunction "A_1") (pintype "passive"))
      (node (ref "U28") (pin "16") (pinfunction "VCC_16") (pintype "power_in"))
      (node (ref "U29") (pin "4") (pinfunction "+Vo_4") (pintype "passive"))
      (node (ref "U30") (pin "8") (pinfunction "VDD2_8") (pintype "passive"))
    )
    (net (code "74") (name "RS5V2") (class "Default")
      (node (ref "C83") (pin "1") (pinfunction "1_1") (pintype "passive"))
      (node (ref "C85") (pin "1") (pinfunction "1_1") (pintype "passive"))
      (node (ref "C86") (pin "1") (pinfunction "1_1") (pintype "passive"))
      (node (ref "C88") (pin "1") (pinfunction "1_1") (pintype "passive"))
      (node (ref "C89") (pin "2") (pinfunction "2_2") (pintype "passive"))
      (node (ref "U31") (pin "16") (pinfunction "VCC_16") (pintype "power_in"))
      (node (ref "U32") (pin "4") (pinfunction "+Vo_4") (pintype "passive"))
      (node (ref "U33") (pin "8") (pinfunction "VDD2_8") (pintype "passive"))
    )
    (net (code "75") (name "RS5V3") (class "Default")
      (node (ref "C100") (pin "1") (pinfunction "1_1") (pintype "passive"))
      (node (ref "C101") (pin "2") (pinfunction "2_2") (pintype "passive"))
      (node (ref "C102") (pin "2") (pinfunction "2_2") (pintype "passive"))
      (node (ref "C93") (pin "1") (pinfunction "1_1") (pintype "passive"))
      (node (ref "C95") (pin "1") (pinfunction "1_1") (pintype "passive"))
      (node (ref "C96") (pin "1") (pinfunction "1_1") (pintype "passive"))
      (node (ref "R104") (pin "1") (pinfunction "1_1") (pintype "passive"))
      (node (ref "U34") (pin "16") (pinfunction "VCC_16") (pintype "power_in"))
      (node (ref "U35") (pin "4") (pinfunction "+Vo_4") (pintype "passive"))
      (node (ref "U36") (pin "8") (pinfunction "VDD2_8") (pintype "passive"))
      (node (ref "U37") (pin "8") (pinfunction "VCC_8") (pintype "power_in"))
      (node (ref "U38") (pin "4") (pinfunction "C_4") (pintype "passive"))
    )
    (net (code "76") (name "VCC3V3") (class "Default")
      (node (ref "U27") (pin "4") (pinfunction "C_4") (pintype "passive"))
      (node (ref "U30") (pin "1") (pinfunction "VDD1_1") (pintype "passive"))
      (node (ref "U33") (pin "1") (pinfunction "VDD1_1") (pintype "passive"))
      (node (ref "U36") (pin "1") (pinfunction "VDD1_1") (pintype "passive"))
      (node (ref "U38") (pin "1") (pinfunction "A_1") (pintype "passive"))
    )
    (net (code "77") (name "VCC5V") (class "Default")
      (node (ref "C76") (pin "2") (pinfunction "2_2") (pintype "passive"))
      (node (ref "C77") (pin "1") (pinfunction "1_1") (pintype "passive"))
      (node (ref "C87") (pin "1") (pinfunction "1_1") (pintype "passive"))
      (node (ref "C99") (pin "1") (pinfunction "1_1") (pintype "passive"))
      (node (ref "U29") (pin "2") (pinfunction "Vin_2") (pintype "passive"))
      (node (ref "U32") (pin "2") (pinfunction "Vin_2") (pintype "passive"))
      (node (ref "U35") (pin "2") (pinfunction "Vin_2") (pintype "passive"))
    )
    (net (code "78") (name "unconnected-(P13-Pad1)") (class "Default")
      (node (ref "P13") (pin "1") (pinfunction "1_1") (pintype "passive"))
    )
    (net (code "79") (name "unconnected-(P13-Pad6)") (class "Default")
      (node (ref "P13") (pin "6") (pinfunction "6_6") (pintype "passive"))
    )
    (net (code "80") (name "unconnected-(P13-Pad7)") (class "Default")
      (node (ref "P13") (pin "7") (pinfunction "7_7") (pintype "passive"))
    )
    (net (code "81") (name "unconnected-(P13-Pad8)") (class "Default")
      (node (ref "P13") (pin "8") (pinfunction "8_8") (pintype "passive"))
    )
    (net (code "82") (name "unconnected-(P13-Pad9)") (class "Default")
      (node (ref "P13") (pin "9") (pinfunction "9_9") (pintype "passive"))
    )
    (net (code "83") (name "unconnected-(U28-T1OUT-Pad14)") (class "Default")
      (node (ref "U28") (pin "14") (pinfunction "T1OUT_14") (pintype "output"))
    )
    (net (code "84") (name "unconnected-(U31-R2OUT-Pad9)") (class "Default")
      (node (ref "U31") (pin "9") (pinfunction "R2OUT_9") (pintype "output"))
    )
    (net (code "85") (name "unconnected-(U31-T2OUT-Pad7)") (class "Default")
      (node (ref "U31") (pin "7") (pinfunction "T2OUT_7") (pintype "output"))
    )
    (net (code "86") (name "unconnected-(U34-R2OUT-Pad9)") (class "Default")
      (node (ref "U34") (pin "9") (pinfunction "R2OUT_9") (pintype "output"))
    )
    (net (code "87") (name "unconnected-(U34-T2OUT-Pad7)") (class "Default")
      (node (ref "U34") (pin "7") (pinfunction "T2OUT_7") (pintype "output"))
    )
  )
)
